# SCH_circuit-2_2025-10-18.net
KiCad netlist of a schematic drawn in EasyEDA
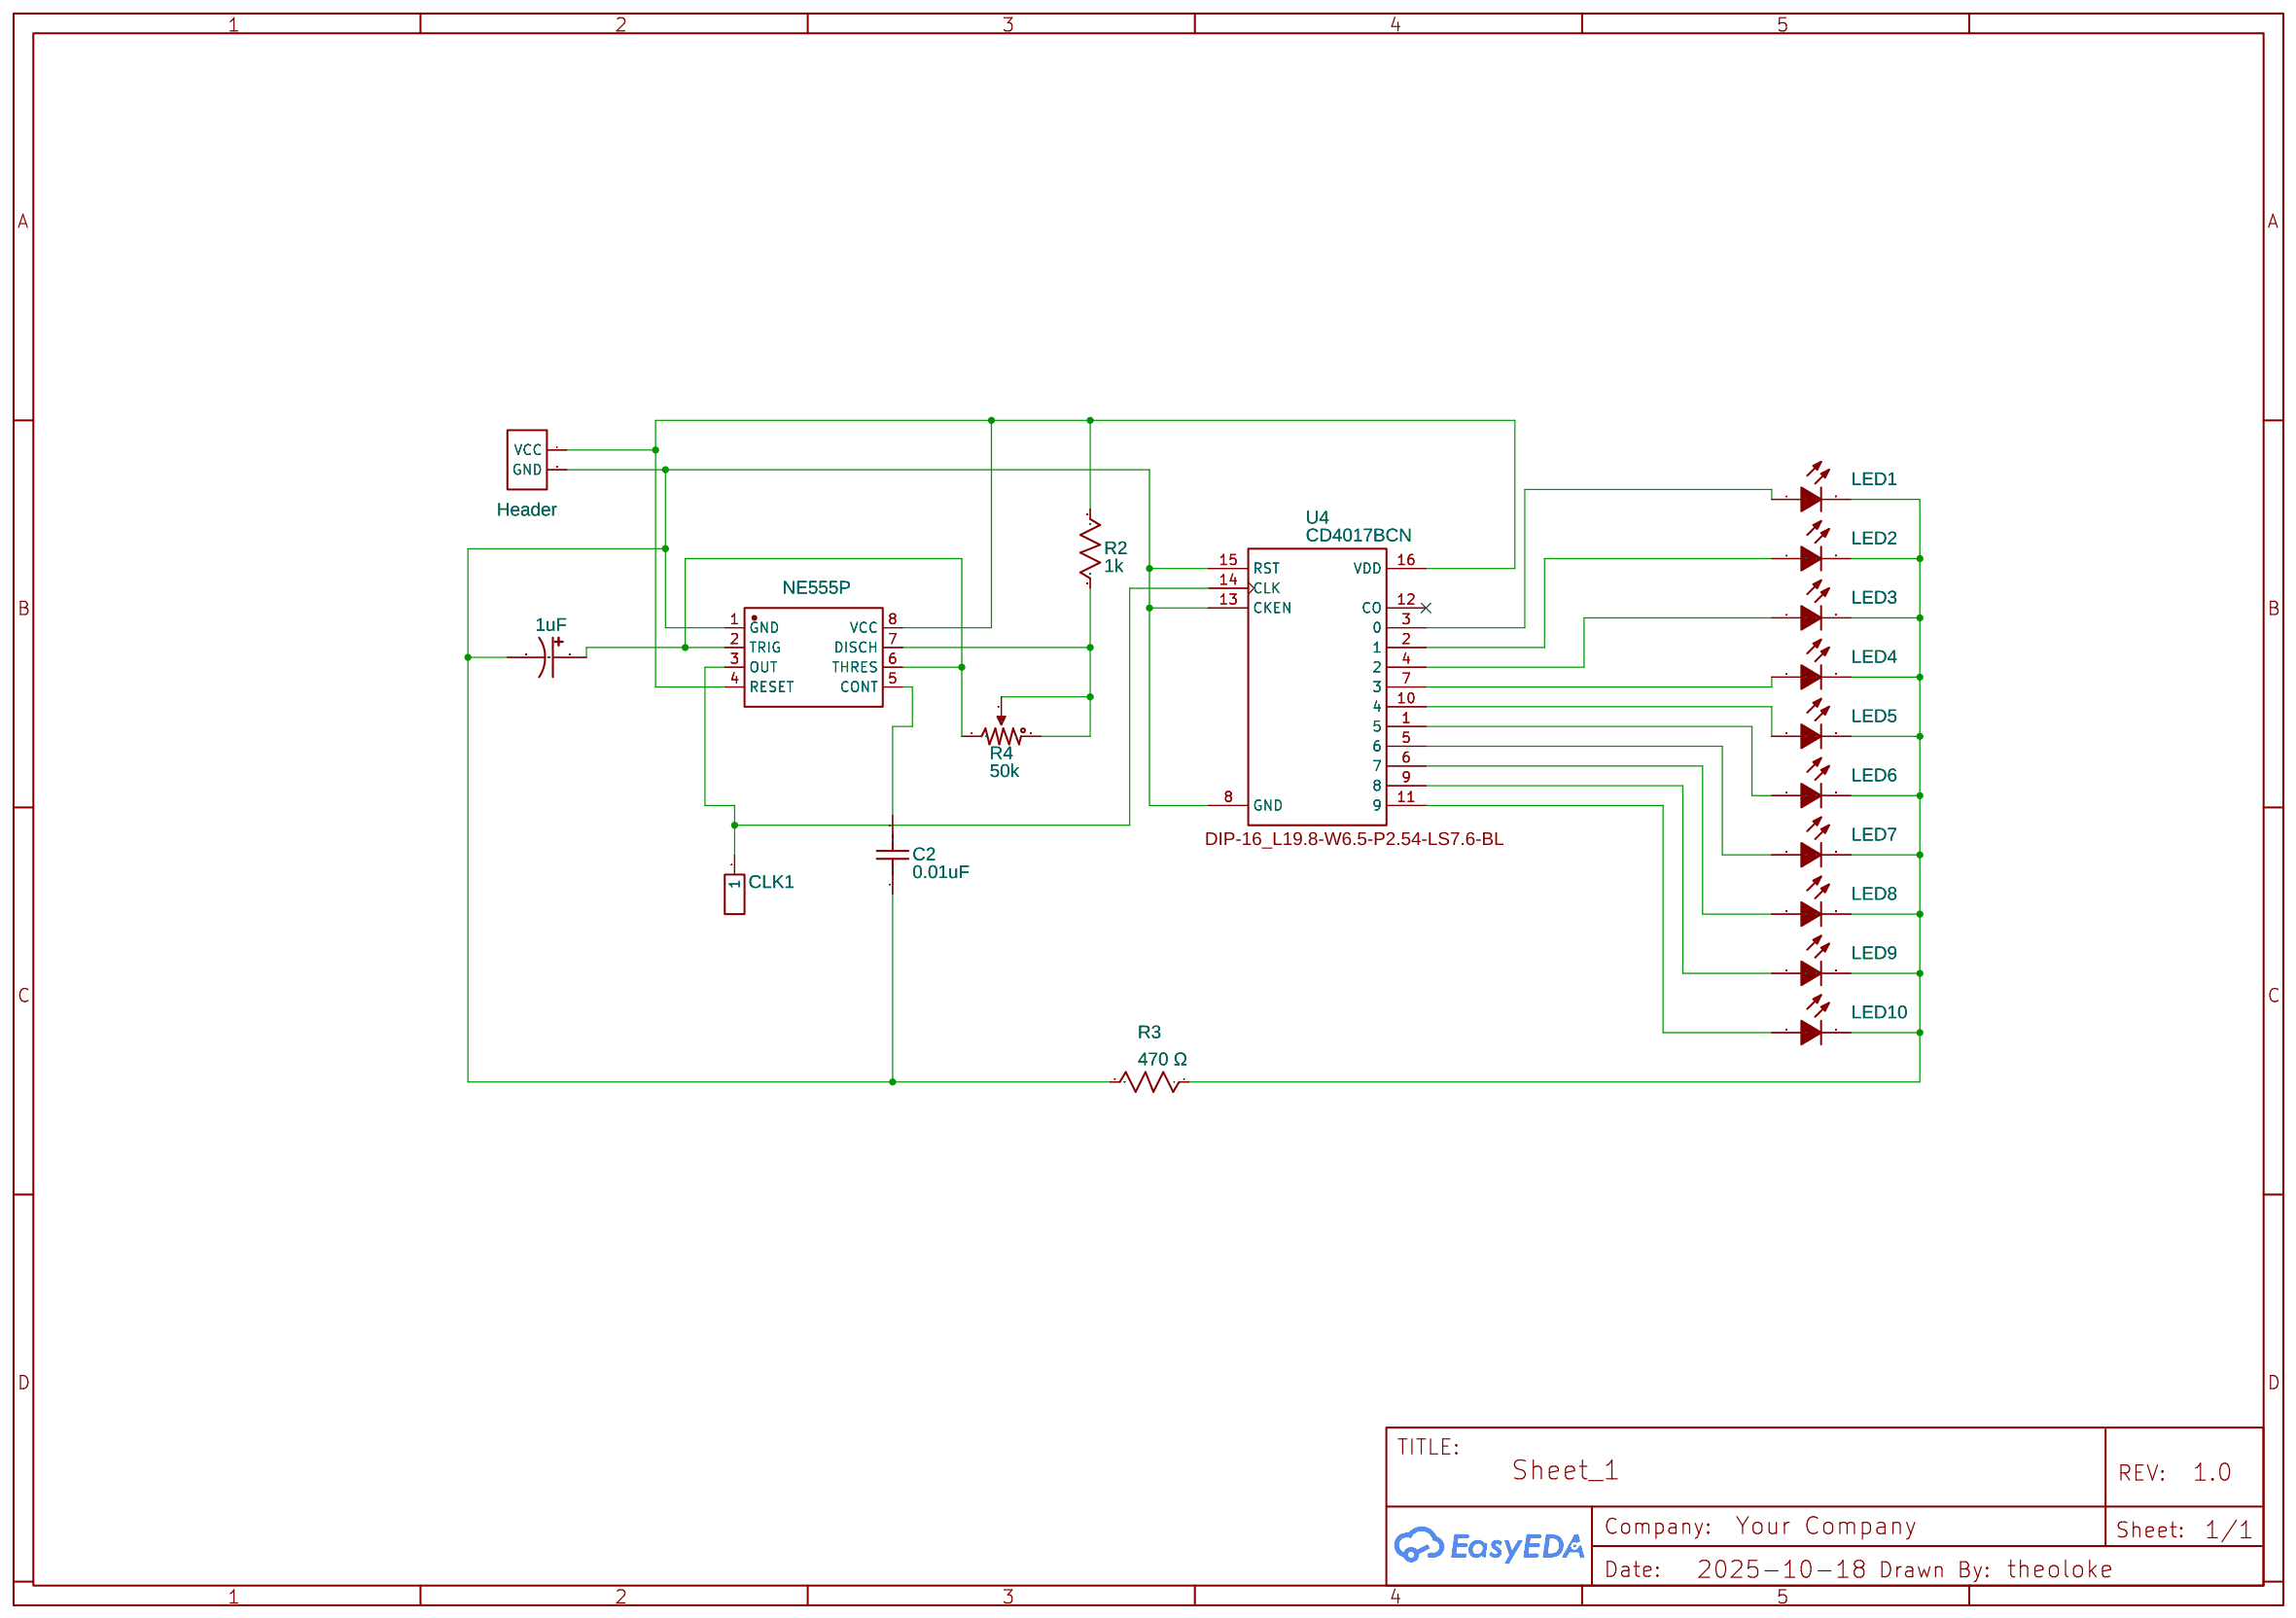
[diagram p0: schematic sheet]

(export (version "E")
  (design (tool "Eeschema 10.0.6"))
  (components
    (comp (ref "C1")
      (value "1uF")
      (fields (field (name "Manufacturer Part") "UVZ1H010MDD") (field (name "Manufacturer") "Nichicon(尼吉康)"))
      (libsource (lib "") (part "UVZ1H010MDD"))
    )
    (comp (ref "C2") (value "0.01uF") (libsource (lib "") (part "C_0603_US")))
    (comp (ref "CLK1")
      (value "C81276")
      (fields
        (field (name "Manufacturer Part") "2.54-1*1P针")
        (field (name "Manufacturer") "BOOMELE(Boom Precision Elec)")
      )
      (libsource (lib "") (part "Header-Male-2.54_1x1"))
    )
    (comp (ref "H1") (value "Header") (libsource (lib "") (part "HEADER-FEMALE-2.54_1X2")))
    (comp (ref "LED1") (value "LED_5MM") (libsource (lib "") (part "LED_5MM")))
    (comp (ref "LED2") (value "LED_5MM") (libsource (lib "") (part "LED_5MM")))
    (comp (ref "LED3") (value "LED_5MM") (libsource (lib "") (part "LED_5MM")))
    (comp (ref "LED4") (value "LED_5MM") (libsource (lib "") (part "LED_5MM")))
    (comp (ref "LED5") (value "LED_5MM") (libsource (lib "") (part "LED_5MM")))
    (comp (ref "LED6") (value "LED_5MM") (libsource (lib "") (part "LED_5MM")))
    (comp (ref "LED7") (value "LED_5MM") (libsource (lib "") (part "LED_5MM")))
    (comp (ref "LED8") (value "LED_5MM") (libsource (lib "") (part "LED_5MM")))
    (comp (ref "LED9") (value "LED_5MM") (libsource (lib "") (part "LED_5MM")))
    (comp (ref "LED10") (value "LED_5MM") (libsource (lib "") (part "LED_5MM")))
    (comp (ref "R2")
      (value "1k")
      (fields (field (name "Manufacturer Part") "?"))
      (libsource (lib "") (part "Resistor"))
    )
    (comp (ref "R3")
      (value "470 Ω")
      (fields (field (name "Manufacturer Part") "?"))
      (libsource (lib "") (part "Resistor_1"))
    )
    (comp (ref "R4")
      (value "50k")
      (fields (field (name "Manufacturer Part") "?"))
      (libsource (lib "") (part "Potentiometer"))
    )
    (comp (ref "U2")
      (value "NE555P")
      (fields (field (name "Manufacturer") "TI(德州仪器)"))
      (libsource (lib "") (part "NE555P"))
    )
    (comp (ref "U4") (value "CD4017BCN") (libsource (lib "") (part "CD4017BCN")))
  )
  (nets
    (net (code "1") (name "Net-(H1-GND)") (class "Default")
      (node (ref "C1") (pin "2") (pinfunction "2_2") (pintype "unspecified"))
      (node (ref "C2") (pin "1") (pinfunction "1_1") (pintype "unspecified"))
      (node (ref "H1") (pin "2") (pinfunction "GND_2") (pintype "unspecified"))
      (node (ref "R3") (pin "2") (pinfunction "2_2") (pintype "unspecified"))
      (node (ref "U2") (pin "1") (pinfunction "GND_1") (pintype "unspecified"))
      (node (ref "U4") (pin "13") (pinfunction "CKEN_13") (pintype "unspecified"))
      (node (ref "U4") (pin "15") (pinfunction "RST_15") (pintype "unspecified"))
      (node (ref "U4") (pin "8") (pinfunction "GND_8") (pintype "passive"))
    )
    (net (code "2") (name "Net-(H1-VCC)") (class "Default")
      (node (ref "H1") (pin "1") (pinfunction "VCC_1") (pintype "unspecified"))
      (node (ref "R2") (pin "1") (pinfunction "1_1") (pintype "unspecified"))
      (node (ref "U2") (pin "4") (pinfunction "RESET_4") (pintype "unspecified"))
      (node (ref "U2") (pin "8") (pinfunction "VCC_8") (pintype "unspecified"))
      (node (ref "U4") (pin "16") (pinfunction "VDD_16") (pintype "passive"))
    )
    (net (code "3") (name "Net-(LED1-A)") (class "Default")
      (node (ref "LED1") (pin "1") (pinfunction "A_1") (pintype "input"))
      (node (ref "U4") (pin "3") (pinfunction "0_3") (pintype "output"))
    )
    (net (code "4") (name "Net-(LED1-K)") (class "Default")
      (node (ref "LED1") (pin "2") (pinfunction "K_2") (pintype "input"))
      (node (ref "LED10") (pin "2") (pinfunction "K_2") (pintype "input"))
      (node (ref "LED2") (pin "2") (pinfunction "K_2") (pintype "input"))
      (node (ref "LED3") (pin "2") (pinfunction "K_2") (pintype "input"))
      (node (ref "LED4") (pin "2") (pinfunction "K_2") (pintype "input"))
      (node (ref "LED5") (pin "2") (pinfunction "K_2") (pintype "input"))
      (node (ref "LED6") (pin "2") (pinfunction "K_2") (pintype "input"))
      (node (ref "LED7") (pin "2") (pinfunction "K_2") (pintype "input"))
      (node (ref "LED8") (pin "2") (pinfunction "K_2") (pintype "input"))
      (node (ref "LED9") (pin "2") (pinfunction "K_2") (pintype "input"))
      (node (ref "R3") (pin "1") (pinfunction "1_1") (pintype "unspecified"))
    )
    (net (code "5") (name "Net-(LED2-A)") (class "Default")
      (node (ref "LED2") (pin "1") (pinfunction "A_1") (pintype "input"))
      (node (ref "U4") (pin "2") (pinfunction "1_2") (pintype "output"))
    )
    (net (code "6") (name "Net-(LED3-A)") (class "Default")
      (node (ref "LED3") (pin "1") (pinfunction "A_1") (pintype "input"))
      (node (ref "U4") (pin "4") (pinfunction "2_4") (pintype "output"))
    )
    (net (code "7") (name "Net-(LED4-A)") (class "Default")
      (node (ref "LED4") (pin "1") (pinfunction "A_1") (pintype "input"))
      (node (ref "U4") (pin "7") (pinfunction "3_7") (pintype "output"))
    )
    (net (code "8") (name "Net-(LED5-A)") (class "Default")
      (node (ref "LED5") (pin "1") (pinfunction "A_1") (pintype "input"))
      (node (ref "U4") (pin "10") (pinfunction "4_10") (pintype "output"))
    )
    (net (code "9") (name "Net-(LED6-A)") (class "Default")
      (node (ref "LED6") (pin "1") (pinfunction "A_1") (pintype "input"))
      (node (ref "U4") (pin "1") (pinfunction "5_1") (pintype "output"))
    )
    (net (code "10") (name "Net-(LED7-A)") (class "Default")
      (node (ref "LED7") (pin "1") (pinfunction "A_1") (pintype "input"))
      (node (ref "U4") (pin "5") (pinfunction "6_5") (pintype "output"))
    )
    (net (code "11") (name "Net-(LED8-A)") (class "Default")
      (node (ref "LED8") (pin "1") (pinfunction "A_1") (pintype "input"))
      (node (ref "U4") (pin "6") (pinfunction "7_6") (pintype "output"))
    )
    (net (code "12") (name "Net-(LED9-A)") (class "Default")
      (node (ref "LED9") (pin "1") (pinfunction "A_1") (pintype "input"))
      (node (ref "U4") (pin "9") (pinfunction "8_9") (pintype "output"))
    )
    (net (code "13") (name "Net-(LED10-A)") (class "Default")
      (node (ref "LED10") (pin "1") (pinfunction "A_1") (pintype "input"))
      (node (ref "U4") (pin "11") (pinfunction "9_11") (pintype "output"))
    )
    (net (code "14") (name "Net-(R4-2)") (class "Default")
      (node (ref "R2") (pin "2") (pinfunction "2_2") (pintype "unspecified"))
      (node (ref "R4") (pin "2") (pinfunction "3_2") (pintype "unspecified"))
      (node (ref "R4") (pin "3") (pinfunction "2_3") (pintype "unspecified"))
      (node (ref "U2") (pin "7") (pinfunction "DISCH_7") (pintype "unspecified"))
    )
    (net (code "15") (name "Net-(U2-CONT)") (class "Default")
      (node (ref "C2") (pin "2") (pinfunction "2_2") (pintype "unspecified"))
      (node (ref "U2") (pin "5") (pinfunction "CONT_5") (pintype "unspecified"))
    )
    (net (code "16") (name "Net-(U2-OUT)") (class "Default")
      (node (ref "CLK1") (pin "1") (pinfunction "1_1") (pintype "unspecified"))
      (node (ref "U2") (pin "3") (pinfunction "OUT_3") (pintype "unspecified"))
      (node (ref "U4") (pin "14") (pinfunction "CLK_14") (pintype "unspecified"))
    )
    (net (code "17") (name "Net-(U2-THRES)") (class "Default")
      (node (ref "C1") (pin "1") (pinfunction "1_1") (pintype "unspecified"))
      (node (ref "R4") (pin "1") (pinfunction "1_1") (pintype "unspecified"))
      (node (ref "U2") (pin "2") (pinfunction "TRIG_2") (pintype "unspecified"))
      (node (ref "U2") (pin "6") (pinfunction "THRES_6") (pintype "unspecified"))
    )
    (net (code "18") (name "unconnected-(U4-CO-Pad12)") (class "Default")
      (node (ref "U4") (pin "12") (pinfunction "CO_12") (pintype "output+no_connect"))
    )
  )
)
